# design.net
KiCad netlist of a schematic drawn in Altium Designer
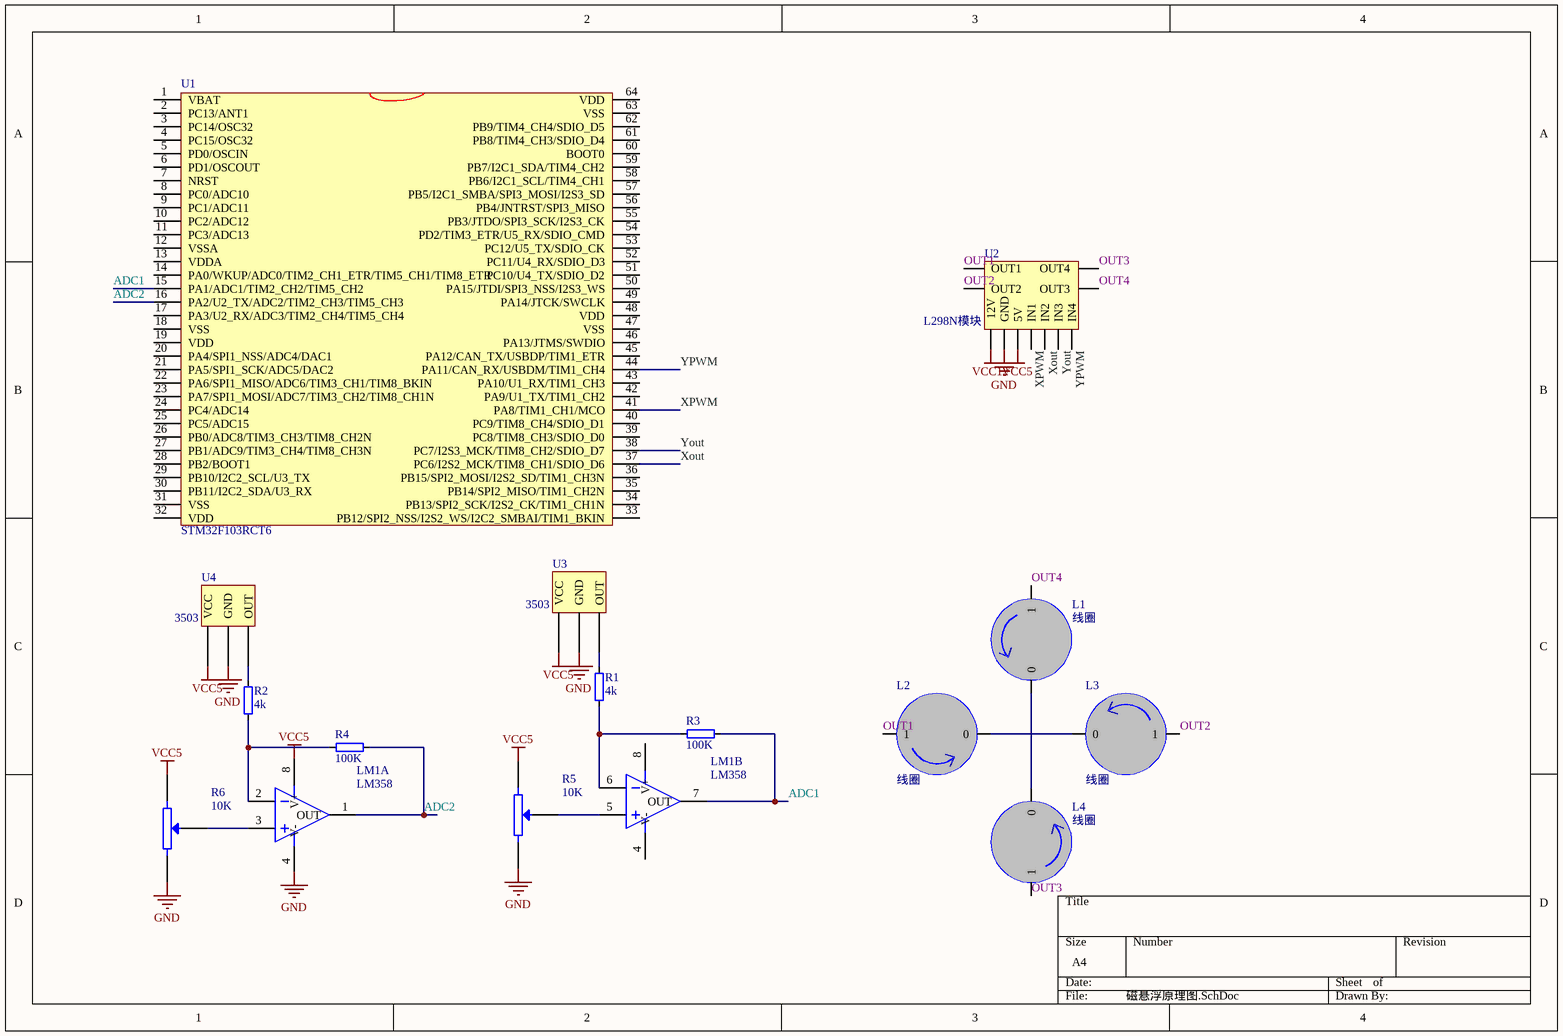
[diagram p0: 磁悬浮原理图.SchDoc]

(export (version "E")
  (design (tool "Eeschema 10.0.6"))
  (components
    (comp (ref "L1") (value "线圈") (footprint "线圈") (libsource (lib "红外报警") (part "线圈")))
    (comp (ref "L2") (value "线圈") (footprint "线圈") (libsource (lib "红外报警") (part "线圈")))
    (comp (ref "L3") (value "线圈") (footprint "线圈") (libsource (lib "红外报警") (part "线圈")))
    (comp (ref "L4") (value "线圈") (footprint "线圈") (libsource (lib "红外报警") (part "线圈")))
    (comp (ref "LM1") (value "LM358") (footprint "SOIC-8") (libsource (lib "红外报警") (part "LM358")))
    (comp (ref "R1") (value "4k") (footprint "RES_0805") (libsource (lib "红外报警") (part "RES")))
    (comp (ref "R2") (value "4k") (footprint "RES_0805") (libsource (lib "红外报警") (part "RES")))
    (comp (ref "R3") (value "100K") (footprint "RES_0805") (libsource (lib "红外报警") (part "RES")))
    (comp (ref "R4") (value "100K") (footprint "RES_0805") (libsource (lib "红外报警") (part "RES")))
    (comp (ref "R5")
      (value "10K")
      (footprint "VR")
      (description "Potentiometer")
      (libsource (lib "红外报警") (part "RESVR"))
    )
    (comp (ref "R6")
      (value "10K")
      (footprint "VR")
      (description "Potentiometer")
      (libsource (lib "红外报警") (part "RESVR"))
    )
    (comp (ref "U1")
      (value "STM32F103RCT6")
      (footprint "LQFP64")
      (libsource (lib "MiniSTM32 V3.0封装库") (part "STM32F103RDT6"))
    )
    (comp (ref "U2") (value "L298N模块") (libsource (lib "红外报警") (part "L298N")))
    (comp (ref "U3") (value "3503") (libsource (lib "红外报警") (part "3503")))
    (comp (ref "U4") (value "3503") (libsource (lib "红外报警") (part "3503")))
  )
  (nets
    (net (code "1") (name "/ADC1") (class "Default")
      (node (ref "LM1") (pin "7") (pinfunction "OUT_7") (pintype "passive"))
      (node (ref "R3") (pin "1") (pinfunction "1_1") (pintype "passive"))
      (node (ref "U1") (pin "15") (pinfunction "PA1/ADC1/TIM2_CH2/TIM5_CH2_15") (pintype "passive"))
    )
    (net (code "2") (name "/ADC2") (class "Default")
      (node (ref "LM1") (pin "1") (pinfunction "OUT_1") (pintype "passive"))
      (node (ref "R4") (pin "1") (pinfunction "1_1") (pintype "passive"))
      (node (ref "U1") (pin "16") (pinfunction "PA2/U2_TX/ADC2/TIM2_CH3/TIM5_CH3_16") (pintype "passive"))
    )
    (net (code "3") (name "/OUT1") (class "Default")
      (node (ref "L2") (pin "1") (pinfunction "1_1") (pintype "passive"))
      (node (ref "U2") (pin "10") (pinfunction "OUT1_10") (pintype "passive"))
    )
    (net (code "4") (name "/OUT2") (class "Default")
      (node (ref "L3") (pin "1") (pinfunction "1_1") (pintype "passive"))
      (node (ref "U2") (pin "9") (pinfunction "OUT2_9") (pintype "passive"))
    )
    (net (code "5") (name "/OUT3") (class "Default")
      (node (ref "L4") (pin "1") (pinfunction "1_1") (pintype "passive"))
      (node (ref "U2") (pin "11") (pinfunction "OUT4_11") (pintype "passive"))
    )
    (net (code "6") (name "/OUT4") (class "Default")
      (node (ref "L1") (pin "1") (pinfunction "1_1") (pintype "passive"))
      (node (ref "U2") (pin "12") (pinfunction "OUT3_12") (pintype "passive"))
    )
    (net (code "7") (name "/XPWM") (class "Default")
      (node (ref "U1") (pin "41") (pinfunction "PA8/TIM1_CH1/MCO_41") (pintype "passive"))
      (node (ref "U2") (pin "4") (pinfunction "IN1_4") (pintype "passive"))
    )
    (net (code "8") (name "/Xout") (class "Default")
      (node (ref "U1") (pin "37") (pinfunction "PC6/I2S2_MCK/TIM8_CH1/SDIO_D6_37") (pintype "passive"))
      (node (ref "U2") (pin "5") (pinfunction "IN2_5") (pintype "passive"))
    )
    (net (code "9") (name "/YPWM") (class "Default")
      (node (ref "U1") (pin "44") (pinfunction "PA11/CAN_RX/USBDM/TIM1_CH4_44") (pintype "passive"))
      (node (ref "U2") (pin "7") (pinfunction "IN4_7") (pintype "passive"))
    )
    (net (code "10") (name "/Yout") (class "Default")
      (node (ref "U1") (pin "38") (pinfunction "PC7/I2S3_MCK/TIM8_CH2/SDIO_D7_38") (pintype "passive"))
      (node (ref "U2") (pin "6") (pinfunction "IN3_6") (pintype "passive"))
    )
    (net (code "11") (name "GND") (class "Default")
      (node (ref "LM1") (pin "4") (pinfunction "V-_4") (pintype "passive"))
      (node (ref "R5") (pin "2") (pinfunction "2_2") (pintype "passive"))
      (node (ref "R6") (pin "2") (pinfunction "2_2") (pintype "passive"))
      (node (ref "U2") (pin "2") (pinfunction "GND_2") (pintype "passive"))
      (node (ref "U3") (pin "2") (pinfunction "GND_2") (pintype "passive"))
      (node (ref "U4") (pin "2") (pinfunction "GND_2") (pintype "passive"))
    )
    (net (code "12") (name "Net-(L1-Pad0)") (class "Default")
      (node (ref "L1") (pin "0") (pinfunction "0_0") (pintype "passive"))
      (node (ref "L4") (pin "0") (pinfunction "0_0") (pintype "passive"))
    )
    (net (code "13") (name "Net-(L2-Pad0)") (class "Default")
      (node (ref "L2") (pin "0") (pinfunction "0_0") (pintype "passive"))
      (node (ref "L3") (pin "0") (pinfunction "0_0") (pintype "passive"))
    )
    (net (code "14") (name "Net-(LM1A-IN+)") (class "Default")
      (node (ref "LM1") (pin "3") (pinfunction "IN+_3") (pintype "passive"))
      (node (ref "R6") (pin "3") (pinfunction "W_3") (pintype "passive"))
    )
    (net (code "15") (name "Net-(LM1A-IN-)") (class "Default")
      (node (ref "LM1") (pin "2") (pinfunction "IN-_2") (pintype "passive"))
      (node (ref "R2") (pin "1") (pinfunction "1_1") (pintype "passive"))
      (node (ref "R4") (pin "2") (pinfunction "2_2") (pintype "passive"))
    )
    (net (code "16") (name "Net-(LM1B-IN+)") (class "Default")
      (node (ref "LM1") (pin "5") (pinfunction "IN+_5") (pintype "passive"))
      (node (ref "R5") (pin "3") (pinfunction "W_3") (pintype "passive"))
    )
    (net (code "17") (name "Net-(LM1B-IN-)") (class "Default")
      (node (ref "LM1") (pin "6") (pinfunction "IN-_6") (pintype "passive"))
      (node (ref "R1") (pin "1") (pinfunction "1_1") (pintype "passive"))
      (node (ref "R3") (pin "2") (pinfunction "2_2") (pintype "passive"))
    )
    (net (code "18") (name "Net-(U3-OUT)") (class "Default")
      (node (ref "R1") (pin "2") (pinfunction "2_2") (pintype "passive"))
      (node (ref "U3") (pin "3") (pinfunction "OUT_3") (pintype "passive"))
    )
    (net (code "19") (name "Net-(U4-OUT)") (class "Default")
      (node (ref "R2") (pin "2") (pinfunction "2_2") (pintype "passive"))
      (node (ref "U4") (pin "3") (pinfunction "OUT_3") (pintype "passive"))
    )
    (net (code "20") (name "VCC5") (class "Default")
      (node (ref "LM1") (pin "8") (pinfunction "V+_8") (pintype "passive"))
      (node (ref "R5") (pin "1") (pinfunction "1_1") (pintype "passive"))
      (node (ref "R6") (pin "1") (pinfunction "1_1") (pintype "passive"))
      (node (ref "U2") (pin "3") (pinfunction "5V_3") (pintype "passive"))
      (node (ref "U3") (pin "1") (pinfunction "VCC_1") (pintype "passive"))
      (node (ref "U4") (pin "1") (pinfunction "VCC_1") (pintype "passive"))
    )
    (net (code "21") (name "VCC12") (class "Default")
      (node (ref "U2") (pin "1") (pinfunction "12V_1") (pintype "passive"))
    )
    (net (code "22") (name "unconnected-(LM1B-V+-Pad8)") (class "Default")
      (node (ref "LM1") (pin "8") (pinfunction "V+_8") (pintype "passive"))
    )
    (net (code "23") (name "unconnected-(LM1B-V--Pad4)") (class "Default")
      (node (ref "LM1") (pin "4") (pinfunction "V-_4") (pintype "passive"))
    )
    (net (code "24") (name "unconnected-(U1-BOOT0-Pad60)") (class "Default")
      (node (ref "U1") (pin "60") (pinfunction "BOOT0_60") (pintype "passive"))
    )
    (net (code "25") (name "unconnected-(U1-NRST-Pad7)") (class "Default")
      (node (ref "U1") (pin "7") (pinfunction "NRST_7") (pintype "passive"))
    )
    (net (code "26") (name "unconnected-(U1-PA0{slash}WKUP{slash}ADC0{slash}TIM2_CH1_ETR{slash}TIM5_CH1{slash}TIM8_ETR-Pad14)") (class "Default")
      (node (ref "U1") (pin "14") (pinfunction "PA0/WKUP/ADC0/TIM2_CH1_ETR/TIM5_CH1/TIM8_ETR_14") (pintype "passive"))
    )
    (net (code "27") (name "unconnected-(U1-PA3{slash}U2_RX{slash}ADC3{slash}TIM2_CH4{slash}TIM5_CH4-Pad17)") (class "Default")
      (node (ref "U1") (pin "17") (pinfunction "PA3/U2_RX/ADC3/TIM2_CH4/TIM5_CH4_17") (pintype "passive"))
    )
    (net (code "28") (name "unconnected-(U1-PA4{slash}SPI1_NSS{slash}ADC4{slash}DAC1-Pad20)") (class "Default")
      (node (ref "U1") (pin "20") (pinfunction "PA4/SPI1_NSS/ADC4/DAC1_20") (pintype "passive"))
    )
    (net (code "29") (name "unconnected-(U1-PA5{slash}SPI1_SCK{slash}ADC5{slash}DAC2-Pad21)") (class "Default")
      (node (ref "U1") (pin "21") (pinfunction "PA5/SPI1_SCK/ADC5/DAC2_21") (pintype "passive"))
    )
    (net (code "30") (name "unconnected-(U1-PA6{slash}SPI1_MISO{slash}ADC6{slash}TIM3_CH1{slash}TIM8_BKIN-Pad22)") (class "Default")
      (node (ref "U1") (pin "22") (pinfunction "PA6/SPI1_MISO/ADC6/TIM3_CH1/TIM8_BKIN_22") (pintype "passive"))
    )
    (net (code "31") (name "unconnected-(U1-PA7{slash}SPI1_MOSI{slash}ADC7{slash}TIM3_CH2{slash}TIM8_CH1N-Pad23)") (class "Default")
      (node (ref "U1") (pin "23") (pinfunction "PA7/SPI1_MOSI/ADC7/TIM3_CH2/TIM8_CH1N_23") (pintype "passive"))
    )
    (net (code "32") (name "unconnected-(U1-PA9{slash}U1_TX{slash}TIM1_CH2-Pad42)") (class "Default")
      (node (ref "U1") (pin "42") (pinfunction "PA9/U1_TX/TIM1_CH2_42") (pintype "passive"))
    )
    (net (code "33") (name "unconnected-(U1-PA10{slash}U1_RX{slash}TIM1_CH3-Pad43)") (class "Default")
      (node (ref "U1") (pin "43") (pinfunction "PA10/U1_RX/TIM1_CH3_43") (pintype "passive"))
    )
    (net (code "34") (name "unconnected-(U1-PA12{slash}CAN_TX{slash}USBDP{slash}TIM1_ETR-Pad45)") (class "Default")
      (node (ref "U1") (pin "45") (pinfunction "PA12/CAN_TX/USBDP/TIM1_ETR_45") (pintype "passive"))
    )
    (net (code "35") (name "unconnected-(U1-PA13{slash}JTMS{slash}SWDIO-Pad46)") (class "Default")
      (node (ref "U1") (pin "46") (pinfunction "PA13/JTMS/SWDIO_46") (pintype "passive"))
    )
    (net (code "36") (name "unconnected-(U1-PA14{slash}JTCK{slash}SWCLK-Pad49)") (class "Default")
      (node (ref "U1") (pin "49") (pinfunction "PA14/JTCK/SWCLK_49") (pintype "passive"))
    )
    (net (code "37") (name "unconnected-(U1-PA15{slash}JTDI{slash}SPI3_NSS{slash}I2S3_WS-Pad50)") (class "Default")
      (node (ref "U1") (pin "50") (pinfunction "PA15/JTDI/SPI3_NSS/I2S3_WS_50") (pintype "passive"))
    )
    (net (code "38") (name "unconnected-(U1-PB0{slash}ADC8{slash}TIM3_CH3{slash}TIM8_CH2N-Pad26)") (class "Default")
      (node (ref "U1") (pin "26") (pinfunction "PB0/ADC8/TIM3_CH3/TIM8_CH2N_26") (pintype "passive"))
    )
    (net (code "39") (name "unconnected-(U1-PB1{slash}ADC9{slash}TIM3_CH4{slash}TIM8_CH3N-Pad27)") (class "Default")
      (node (ref "U1") (pin "27") (pinfunction "PB1/ADC9/TIM3_CH4/TIM8_CH3N_27") (pintype "passive"))
    )
    (net (code "40") (name "unconnected-(U1-PB2{slash}BOOT1-Pad28)") (class "Default")
      (node (ref "U1") (pin "28") (pinfunction "PB2/BOOT1_28") (pintype "passive"))
    )
    (net (code "41") (name "unconnected-(U1-PB3{slash}JTDO{slash}SPI3_SCK{slash}I2S3_CK-Pad55)") (class "Default")
      (node (ref "U1") (pin "55") (pinfunction "PB3/JTDO/SPI3_SCK/I2S3_CK_55") (pintype "passive"))
    )
    (net (code "42") (name "unconnected-(U1-PB4{slash}JNTRST{slash}SPI3_MISO-Pad56)") (class "Default")
      (node (ref "U1") (pin "56") (pinfunction "PB4/JNTRST/SPI3_MISO_56") (pintype "passive"))
    )
    (net (code "43") (name "unconnected-(U1-PB5{slash}I2C1_SMBA{slash}SPI3_MOSI{slash}I2S3_SD-Pad57)") (class "Default")
      (node (ref "U1") (pin "57") (pinfunction "PB5/I2C1_SMBA/SPI3_MOSI/I2S3_SD_57") (pintype "passive"))
    )
    (net (code "44") (name "unconnected-(U1-PB6{slash}I2C1_SCL{slash}TIM4_CH1-Pad58)") (class "Default")
      (node (ref "U1") (pin "58") (pinfunction "PB6/I2C1_SCL/TIM4_CH1_58") (pintype "passive"))
    )
    (net (code "45") (name "unconnected-(U1-PB7{slash}I2C1_SDA{slash}TIM4_CH2-Pad59)") (class "Default")
      (node (ref "U1") (pin "59") (pinfunction "PB7/I2C1_SDA/TIM4_CH2_59") (pintype "passive"))
    )
    (net (code "46") (name "unconnected-(U1-PB8{slash}TIM4_CH3{slash}SDIO_D4-Pad61)") (class "Default")
      (node (ref "U1") (pin "61") (pinfunction "PB8/TIM4_CH3/SDIO_D4_61") (pintype "passive"))
    )
    (net (code "47") (name "unconnected-(U1-PB9{slash}TIM4_CH4{slash}SDIO_D5-Pad62)") (class "Default")
      (node (ref "U1") (pin "62") (pinfunction "PB9/TIM4_CH4/SDIO_D5_62") (pintype "passive"))
    )
    (net (code "48") (name "unconnected-(U1-PB10{slash}I2C2_SCL{slash}U3_TX-Pad29)") (class "Default")
      (node (ref "U1") (pin "29") (pinfunction "PB10/I2C2_SCL/U3_TX_29") (pintype "passive"))
    )
    (net (code "49") (name "unconnected-(U1-PB11{slash}I2C2_SDA{slash}U3_RX-Pad30)") (class "Default")
      (node (ref "U1") (pin "30") (pinfunction "PB11/I2C2_SDA/U3_RX_30") (pintype "passive"))
    )
    (net (code "50") (name "unconnected-(U1-PB12{slash}SPI2_NSS{slash}I2S2_WS{slash}I2C2_SMBAI{slash}TIM1_BKIN-Pad33)") (class "Default")
      (node (ref "U1") (pin "33") (pinfunction "PB12/SPI2_NSS/I2S2_WS/I2C2_SMBAI/TIM1_BKIN_33") (pintype "passive"))
    )
    (net (code "51") (name "unconnected-(U1-PB13{slash}SPI2_SCK{slash}I2S2_CK{slash}TIM1_CH1N-Pad34)") (class "Default")
      (node (ref "U1") (pin "34") (pinfunction "PB13/SPI2_SCK/I2S2_CK/TIM1_CH1N_34") (pintype "passive"))
    )
    (net (code "52") (name "unconnected-(U1-PB14{slash}SPI2_MISO{slash}TIM1_CH2N-Pad35)") (class "Default")
      (node (ref "U1") (pin "35") (pinfunction "PB14/SPI2_MISO/TIM1_CH2N_35") (pintype "passive"))
    )
    (net (code "53") (name "unconnected-(U1-PB15{slash}SPI2_MOSI{slash}I2S2_SD{slash}TIM1_CH3N-Pad36)") (class "Default")
      (node (ref "U1") (pin "36") (pinfunction "PB15/SPI2_MOSI/I2S2_SD/TIM1_CH3N_36") (pintype "passive"))
    )
    (net (code "54") (name "unconnected-(U1-PC0{slash}ADC10-Pad8)") (class "Default")
      (node (ref "U1") (pin "8") (pinfunction "PC0/ADC10_8") (pintype "passive"))
    )
    (net (code "55") (name "unconnected-(U1-PC1{slash}ADC11-Pad9)") (class "Default")
      (node (ref "U1") (pin "9") (pinfunction "PC1/ADC11_9") (pintype "passive"))
    )
    (net (code "56") (name "unconnected-(U1-PC2{slash}ADC12-Pad10)") (class "Default")
      (node (ref "U1") (pin "10") (pinfunction "PC2/ADC12_10") (pintype "passive"))
    )
    (net (code "57") (name "unconnected-(U1-PC3{slash}ADC13-Pad11)") (class "Default")
      (node (ref "U1") (pin "11") (pinfunction "PC3/ADC13_11") (pintype "passive"))
    )
    (net (code "58") (name "unconnected-(U1-PC4{slash}ADC14-Pad24)") (class "Default")
      (node (ref "U1") (pin "24") (pinfunction "PC4/ADC14_24") (pintype "passive"))
    )
    (net (code "59") (name "unconnected-(U1-PC5{slash}ADC15-Pad25)") (class "Default")
      (node (ref "U1") (pin "25") (pinfunction "PC5/ADC15_25") (pintype "passive"))
    )
    (net (code "60") (name "unconnected-(U1-PC8{slash}TIM8_CH3{slash}SDIO_D0-Pad39)") (class "Default")
      (node (ref "U1") (pin "39") (pinfunction "PC8/TIM8_CH3/SDIO_D0_39") (pintype "passive"))
    )
    (net (code "61") (name "unconnected-(U1-PC9{slash}TIM8_CH4{slash}SDIO_D1-Pad40)") (class "Default")
      (node (ref "U1") (pin "40") (pinfunction "PC9/TIM8_CH4/SDIO_D1_40") (pintype "passive"))
    )
    (net (code "62") (name "unconnected-(U1-PC10{slash}U4_TX{slash}SDIO_D2-Pad51)") (class "Default")
      (node (ref "U1") (pin "51") (pinfunction "PC10/U4_TX/SDIO_D2_51") (pintype "passive"))
    )
    (net (code "63") (name "unconnected-(U1-PC11{slash}U4_RX{slash}SDIO_D3-Pad52)") (class "Default")
      (node (ref "U1") (pin "52") (pinfunction "PC11/U4_RX/SDIO_D3_52") (pintype "passive"))
    )
    (net (code "64") (name "unconnected-(U1-PC12{slash}U5_TX{slash}SDIO_CK-Pad53)") (class "Default")
      (node (ref "U1") (pin "53") (pinfunction "PC12/U5_TX/SDIO_CK_53") (pintype "passive"))
    )
    (net (code "65") (name "unconnected-(U1-PC13{slash}ANT1-Pad2)") (class "Default")
      (node (ref "U1") (pin "2") (pinfunction "PC13/ANT1_2") (pintype "passive"))
    )
    (net (code "66") (name "unconnected-(U1-PC14{slash}OSC32-Pad3)") (class "Default")
      (node (ref "U1") (pin "3") (pinfunction "PC14/OSC32_3") (pintype "passive"))
    )
    (net (code "67") (name "unconnected-(U1-PC15{slash}OSC32-Pad4)") (class "Default")
      (node (ref "U1") (pin "4") (pinfunction "PC15/OSC32_4") (pintype "passive"))
    )
    (net (code "68") (name "unconnected-(U1-PD0{slash}OSCIN-Pad5)") (class "Default")
      (node (ref "U1") (pin "5") (pinfunction "PD0/OSCIN_5") (pintype "passive"))
    )
    (net (code "69") (name "unconnected-(U1-PD1{slash}OSCOUT-Pad6)") (class "Default")
      (node (ref "U1") (pin "6") (pinfunction "PD1/OSCOUT_6") (pintype "passive"))
    )
    (net (code "70") (name "unconnected-(U1-PD2{slash}TIM3_ETR{slash}U5_RX{slash}SDIO_CMD-Pad54)") (class "Default")
      (node (ref "U1") (pin "54") (pinfunction "PD2/TIM3_ETR/U5_RX/SDIO_CMD_54") (pintype "passive"))
    )
    (net (code "71") (name "unconnected-(U1-VBAT-Pad1)") (class "Default")
      (node (ref "U1") (pin "1") (pinfunction "VBAT_1") (pintype "passive"))
    )
    (net (code "72") (name "unconnected-(U1-VDD-Pad19)") (class "Default")
      (node (ref "U1") (pin "19") (pinfunction "VDD_19") (pintype "passive"))
    )
    (net (code "73") (name "unconnected-(U1-VDD-Pad32)") (class "Default")
      (node (ref "U1") (pin "32") (pinfunction "VDD_32") (pintype "passive"))
    )
    (net (code "74") (name "unconnected-(U1-VDD-Pad48)") (class "Default")
      (node (ref "U1") (pin "48") (pinfunction "VDD_48") (pintype "passive"))
    )
    (net (code "75") (name "unconnected-(U1-VDD-Pad64)") (class "Default")
      (node (ref "U1") (pin "64") (pinfunction "VDD_64") (pintype "passive"))
    )
    (net (code "76") (name "unconnected-(U1-VDDA-Pad13)") (class "Default")
      (node (ref "U1") (pin "13") (pinfunction "VDDA_13") (pintype "passive"))
    )
    (net (code "77") (name "unconnected-(U1-VSS-Pad18)") (class "Default")
      (node (ref "U1") (pin "18") (pinfunction "VSS_18") (pintype "passive"))
    )
    (net (code "78") (name "unconnected-(U1-VSS-Pad31)") (class "Default")
      (node (ref "U1") (pin "31") (pinfunction "VSS_31") (pintype "passive"))
    )
    (net (code "79") (name "unconnected-(U1-VSS-Pad47)") (class "Default")
      (node (ref "U1") (pin "47") (pinfunction "VSS_47") (pintype "passive"))
    )
    (net (code "80") (name "unconnected-(U1-VSS-Pad63)") (class "Default")
      (node (ref "U1") (pin "63") (pinfunction "VSS_63") (pintype "passive"))
    )
    (net (code "81") (name "unconnected-(U1-VSSA-Pad12)") (class "Default")
      (node (ref "U1") (pin "12") (pinfunction "VSSA_12") (pintype "passive"))
    )
  )
)
